# I-Ching_connection_board_v4_EASYEDA.net
KiCad netlist of a schematic drawn in EasyEDA
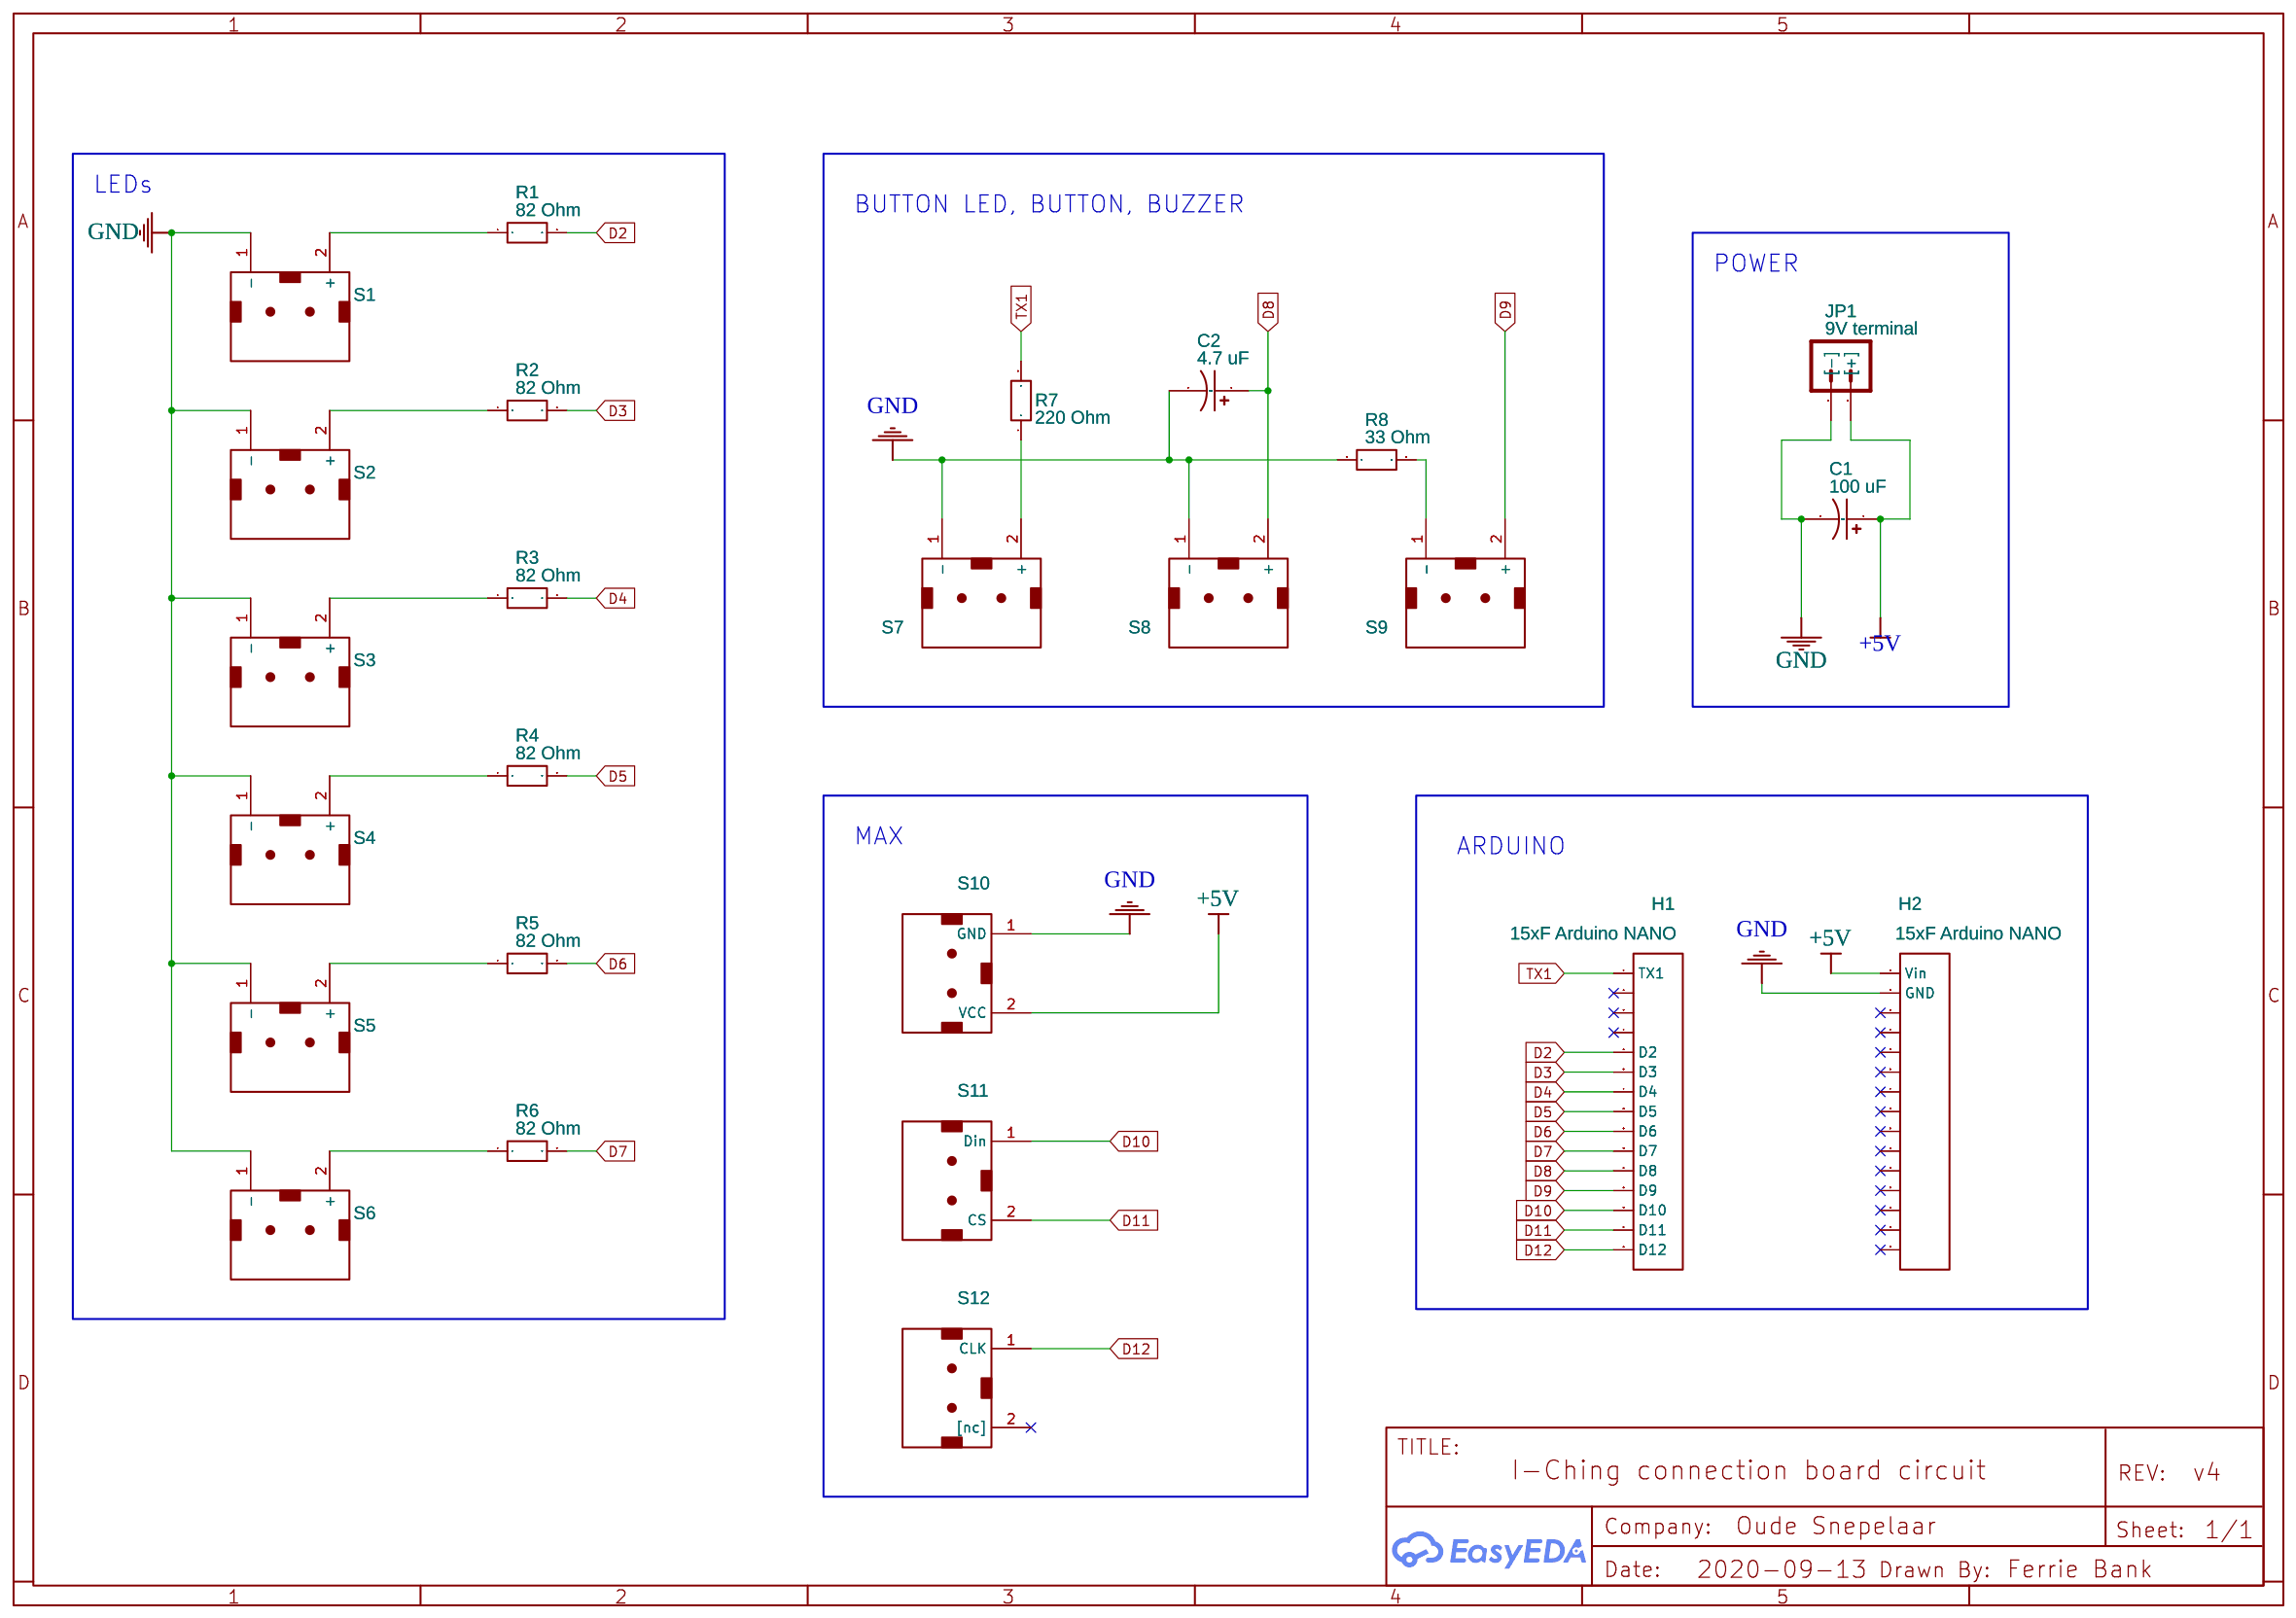
[diagram p0: schematic sheet]

(export (version "E")
  (design (tool "Eeschema 10.0.6"))
  (components
    (comp (ref "C1") (value "100 uF") (libsource (lib "") (part "CE_TH_D10.0×F5.0_US")))
    (comp (ref "C2") (value "4.7 uF") (libsource (lib "") (part "CE_TH_D10.0×F5.0_US")))
    (comp (ref "H1")
      (value "15xF Arduino NANO")
      (fields
        (field (name "BOM_Manufacturer Part") "220S-1*15P H=8.5MM Ytype Gold-plated")
        (field (name "BOM_Supplier Part") "C124408")
      )
      (libsource (lib "") (part "Header-Female-2.54_1x15"))
    )
    (comp (ref "H2")
      (value "15xF Arduino NANO")
      (fields
        (field (name "BOM_Manufacturer Part") "220S-1*15P H=8.5MM Ytype Gold-plated")
        (field (name "BOM_Supplier Part") "C124408")
      )
      (libsource (lib "") (part "Header-Female-2.54_1x15_1"))
    )
    (comp (ref "JP1") (value "9V terminal") (libsource (lib "") (part "Screw Terminal 2-Pin (5mm Pitch)")))
    (comp (ref "R1") (value "82 Ohm") (libsource (lib "") (part "R_0201_EU")))
    (comp (ref "R2") (value "82 Ohm") (libsource (lib "") (part "R_0201_EU")))
    (comp (ref "R3") (value "82 Ohm") (libsource (lib "") (part "R_0201_EU")))
    (comp (ref "R4") (value "82 Ohm") (libsource (lib "") (part "R_0201_EU")))
    (comp (ref "R5") (value "82 Ohm") (libsource (lib "") (part "R_0201_EU")))
    (comp (ref "R6") (value "82 Ohm") (libsource (lib "") (part "R_0201_EU")))
    (comp (ref "R7") (value "220 Ohm") (libsource (lib "") (part "R_0201_EU_1")))
    (comp (ref "R8") (value "33 Ohm") (libsource (lib "") (part "R_0201_EU")))
    (comp (ref "S1") (value "JST 2.0 6mm x 4.5mm") (libsource (lib "") (part "JST 2.0 6mm x 4.5mm_1")))
    (comp (ref "S2") (value "JST 2.0 6mm x 4.5mm") (libsource (lib "") (part "JST 2.0 6mm x 4.5mm_1")))
    (comp (ref "S3") (value "JST 2.0 6mm x 4.5mm") (libsource (lib "") (part "JST 2.0 6mm x 4.5mm_1")))
    (comp (ref "S4") (value "JST 2.0 6mm x 4.5mm") (libsource (lib "") (part "JST 2.0 6mm x 4.5mm_1")))
    (comp (ref "S5") (value "JST 2.0 6mm x 4.5mm") (libsource (lib "") (part "JST 2.0 6mm x 4.5mm_1")))
    (comp (ref "S6") (value "JST 2.0 6mm x 4.5mm") (libsource (lib "") (part "JST 2.0 6mm x 4.5mm_1")))
    (comp (ref "S7") (value "JST 2.0 6mm x 4.5mm") (libsource (lib "") (part "JST 2.0 6mm x 4.5mm_1")))
    (comp (ref "S8") (value "JST 2.0 6mm x 4.5mm") (libsource (lib "") (part "JST 2.0 6mm x 4.5mm_1")))
    (comp (ref "S9") (value "JST 2.0 6mm x 4.5mm") (libsource (lib "") (part "JST 2.0 6mm x 4.5mm_1")))
    (comp (ref "S10") (value "JST 2.0 6mm x 4.5mm") (libsource (lib "") (part "JST 2.0 6mm x 4.5mm_2")))
    (comp (ref "S11") (value "JST 2.0 6mm x 4.5mm") (libsource (lib "") (part "JST 2.0 6mm x 4.5mm")))
    (comp (ref "S12") (value "JST 2.0 6mm x 4.5mm") (libsource (lib "") (part "JST 2.0 6mm x 4.5mm_3")))
  )
  (nets
    (net (code "1") (name "+5V") (class "Default")
      (node (ref "C1") (pin "1") (pinfunction "1_1") (pintype "unspecified"))
      (node (ref "H2") (pin "1") (pinfunction "Vin_1") (pintype "unspecified"))
      (node (ref "JP1") (pin "2") (pinfunction "[+]_2") (pintype "unspecified"))
      (node (ref "S10") (pin "2") (pinfunction "VCC_2") (pintype "unspecified"))
    )
    (net (code "2") (name "D2") (class "Default")
      (node (ref "H1") (pin "5") (pinfunction "D2_5") (pintype "unspecified"))
      (node (ref "R1") (pin "2") (pinfunction "2_2") (pintype "unspecified"))
    )
    (net (code "3") (name "D3") (class "Default")
      (node (ref "H1") (pin "6") (pinfunction "D3_6") (pintype "unspecified"))
      (node (ref "R2") (pin "2") (pinfunction "2_2") (pintype "unspecified"))
    )
    (net (code "4") (name "D4") (class "Default")
      (node (ref "H1") (pin "7") (pinfunction "D4_7") (pintype "unspecified"))
      (node (ref "R3") (pin "2") (pinfunction "2_2") (pintype "unspecified"))
    )
    (net (code "5") (name "D5") (class "Default")
      (node (ref "H1") (pin "8") (pinfunction "D5_8") (pintype "unspecified"))
      (node (ref "R4") (pin "2") (pinfunction "2_2") (pintype "unspecified"))
    )
    (net (code "6") (name "D6") (class "Default")
      (node (ref "H1") (pin "9") (pinfunction "D6_9") (pintype "unspecified"))
      (node (ref "R5") (pin "2") (pinfunction "2_2") (pintype "unspecified"))
    )
    (net (code "7") (name "D7") (class "Default")
      (node (ref "H1") (pin "10") (pinfunction "D7_10") (pintype "unspecified"))
      (node (ref "R6") (pin "2") (pinfunction "2_2") (pintype "unspecified"))
    )
    (net (code "8") (name "D8") (class "Default")
      (node (ref "C2") (pin "1") (pinfunction "1_1") (pintype "unspecified"))
      (node (ref "H1") (pin "11") (pinfunction "D8_11") (pintype "unspecified"))
      (node (ref "S8") (pin "2") (pinfunction "+_2") (pintype "unspecified"))
    )
    (net (code "9") (name "D9") (class "Default")
      (node (ref "H1") (pin "12") (pinfunction "D9_12") (pintype "unspecified"))
      (node (ref "S9") (pin "2") (pinfunction "+_2") (pintype "unspecified"))
    )
    (net (code "10") (name "D10") (class "Default")
      (node (ref "H1") (pin "13") (pinfunction "D10_13") (pintype "unspecified"))
      (node (ref "S11") (pin "1") (pinfunction "Din_1") (pintype "unspecified"))
    )
    (net (code "11") (name "D11") (class "Default")
      (node (ref "H1") (pin "14") (pinfunction "D11_14") (pintype "unspecified"))
      (node (ref "S11") (pin "2") (pinfunction "CS_2") (pintype "unspecified"))
    )
    (net (code "12") (name "D12") (class "Default")
      (node (ref "H1") (pin "15") (pinfunction "D12_15") (pintype "unspecified"))
      (node (ref "S12") (pin "1") (pinfunction "CLK_1") (pintype "unspecified"))
    )
    (net (code "13") (name "GND") (class "Default")
      (node (ref "C1") (pin "2") (pinfunction "2_2") (pintype "unspecified"))
      (node (ref "C2") (pin "2") (pinfunction "2_2") (pintype "unspecified"))
      (node (ref "H2") (pin "2") (pinfunction "GND_2") (pintype "unspecified"))
      (node (ref "JP1") (pin "1") (pinfunction "[-]_1") (pintype "unspecified"))
      (node (ref "R8") (pin "1") (pinfunction "1_1") (pintype "unspecified"))
      (node (ref "S1") (pin "1") (pinfunction "-_1") (pintype "unspecified"))
      (node (ref "S10") (pin "1") (pinfunction "GND_1") (pintype "unspecified"))
      (node (ref "S2") (pin "1") (pinfunction "-_1") (pintype "unspecified"))
      (node (ref "S3") (pin "1") (pinfunction "-_1") (pintype "unspecified"))
      (node (ref "S4") (pin "1") (pinfunction "-_1") (pintype "unspecified"))
      (node (ref "S5") (pin "1") (pinfunction "-_1") (pintype "unspecified"))
      (node (ref "S6") (pin "1") (pinfunction "-_1") (pintype "unspecified"))
      (node (ref "S7") (pin "1") (pinfunction "-_1") (pintype "unspecified"))
      (node (ref "S8") (pin "1") (pinfunction "-_1") (pintype "unspecified"))
    )
    (net (code "14") (name "Net-(S1-+)") (class "Default")
      (node (ref "R1") (pin "1") (pinfunction "1_1") (pintype "unspecified"))
      (node (ref "S1") (pin "2") (pinfunction "+_2") (pintype "unspecified"))
    )
    (net (code "15") (name "Net-(S2-+)") (class "Default")
      (node (ref "R2") (pin "1") (pinfunction "1_1") (pintype "unspecified"))
      (node (ref "S2") (pin "2") (pinfunction "+_2") (pintype "unspecified"))
    )
    (net (code "16") (name "Net-(S3-+)") (class "Default")
      (node (ref "R3") (pin "1") (pinfunction "1_1") (pintype "unspecified"))
      (node (ref "S3") (pin "2") (pinfunction "+_2") (pintype "unspecified"))
    )
    (net (code "17") (name "Net-(S4-+)") (class "Default")
      (node (ref "R4") (pin "1") (pinfunction "1_1") (pintype "unspecified"))
      (node (ref "S4") (pin "2") (pinfunction "+_2") (pintype "unspecified"))
    )
    (net (code "18") (name "Net-(S5-+)") (class "Default")
      (node (ref "R5") (pin "1") (pinfunction "1_1") (pintype "unspecified"))
      (node (ref "S5") (pin "2") (pinfunction "+_2") (pintype "unspecified"))
    )
    (net (code "19") (name "Net-(S6-+)") (class "Default")
      (node (ref "R6") (pin "1") (pinfunction "1_1") (pintype "unspecified"))
      (node (ref "S6") (pin "2") (pinfunction "+_2") (pintype "unspecified"))
    )
    (net (code "20") (name "Net-(S7-+)") (class "Default")
      (node (ref "R7") (pin "1") (pinfunction "1_1") (pintype "unspecified"))
      (node (ref "S7") (pin "2") (pinfunction "+_2") (pintype "unspecified"))
    )
    (net (code "21") (name "Net-(S9--)") (class "Default")
      (node (ref "R8") (pin "2") (pinfunction "2_2") (pintype "unspecified"))
      (node (ref "S9") (pin "1") (pinfunction "-_1") (pintype "unspecified"))
    )
    (net (code "22") (name "TX1") (class "Default")
      (node (ref "H1") (pin "1") (pinfunction "TX1_1") (pintype "unspecified"))
      (node (ref "R7") (pin "2") (pinfunction "2_2") (pintype "unspecified"))
    )
    (net (code "23") (name "unconnected-(H1-Pad2)") (class "Default")
      (node (ref "H1") (pin "2") (pintype "unspecified+no_connect"))
    )
    (net (code "24") (name "unconnected-(H1-Pad3)") (class "Default")
      (node (ref "H1") (pin "3") (pintype "unspecified+no_connect"))
    )
    (net (code "25") (name "unconnected-(H1-Pad4)") (class "Default")
      (node (ref "H1") (pin "4") (pintype "unspecified+no_connect"))
    )
    (net (code "26") (name "unconnected-(H2-Pad3)") (class "Default")
      (node (ref "H2") (pin "3") (pintype "unspecified+no_connect"))
    )
    (net (code "27") (name "unconnected-(H2-Pad4)") (class "Default")
      (node (ref "H2") (pin "4") (pintype "unspecified+no_connect"))
    )
    (net (code "28") (name "unconnected-(H2-Pad5)") (class "Default")
      (node (ref "H2") (pin "5") (pintype "unspecified+no_connect"))
    )
    (net (code "29") (name "unconnected-(H2-Pad6)") (class "Default")
      (node (ref "H2") (pin "6") (pintype "unspecified+no_connect"))
    )
    (net (code "30") (name "unconnected-(H2-Pad7)") (class "Default")
      (node (ref "H2") (pin "7") (pintype "unspecified+no_connect"))
    )
    (net (code "31") (name "unconnected-(H2-Pad8)") (class "Default")
      (node (ref "H2") (pin "8") (pintype "unspecified+no_connect"))
    )
    (net (code "32") (name "unconnected-(H2-Pad9)") (class "Default")
      (node (ref "H2") (pin "9") (pintype "unspecified+no_connect"))
    )
    (net (code "33") (name "unconnected-(H2-Pad10)") (class "Default")
      (node (ref "H2") (pin "10") (pintype "unspecified+no_connect"))
    )
    (net (code "34") (name "unconnected-(H2-Pad11)") (class "Default")
      (node (ref "H2") (pin "11") (pintype "unspecified+no_connect"))
    )
    (net (code "35") (name "unconnected-(H2-Pad12)") (class "Default")
      (node (ref "H2") (pin "12") (pintype "unspecified+no_connect"))
    )
    (net (code "36") (name "unconnected-(H2-Pad13)") (class "Default")
      (node (ref "H2") (pin "13") (pintype "unspecified+no_connect"))
    )
    (net (code "37") (name "unconnected-(H2-Pad14)") (class "Default")
      (node (ref "H2") (pin "14") (pintype "unspecified+no_connect"))
    )
    (net (code "38") (name "unconnected-(H2-Pad15)") (class "Default")
      (node (ref "H2") (pin "15") (pintype "unspecified+no_connect"))
    )
    (net (code "39") (name "unconnected-(S12-[nc]-Pad2)") (class "Default")
      (node (ref "S12") (pin "2") (pinfunction "[nc]_2") (pintype "unspecified+no_connect"))
    )
  )
)
